# ADC.net
KiCad netlist of a schematic drawn in EAGLE
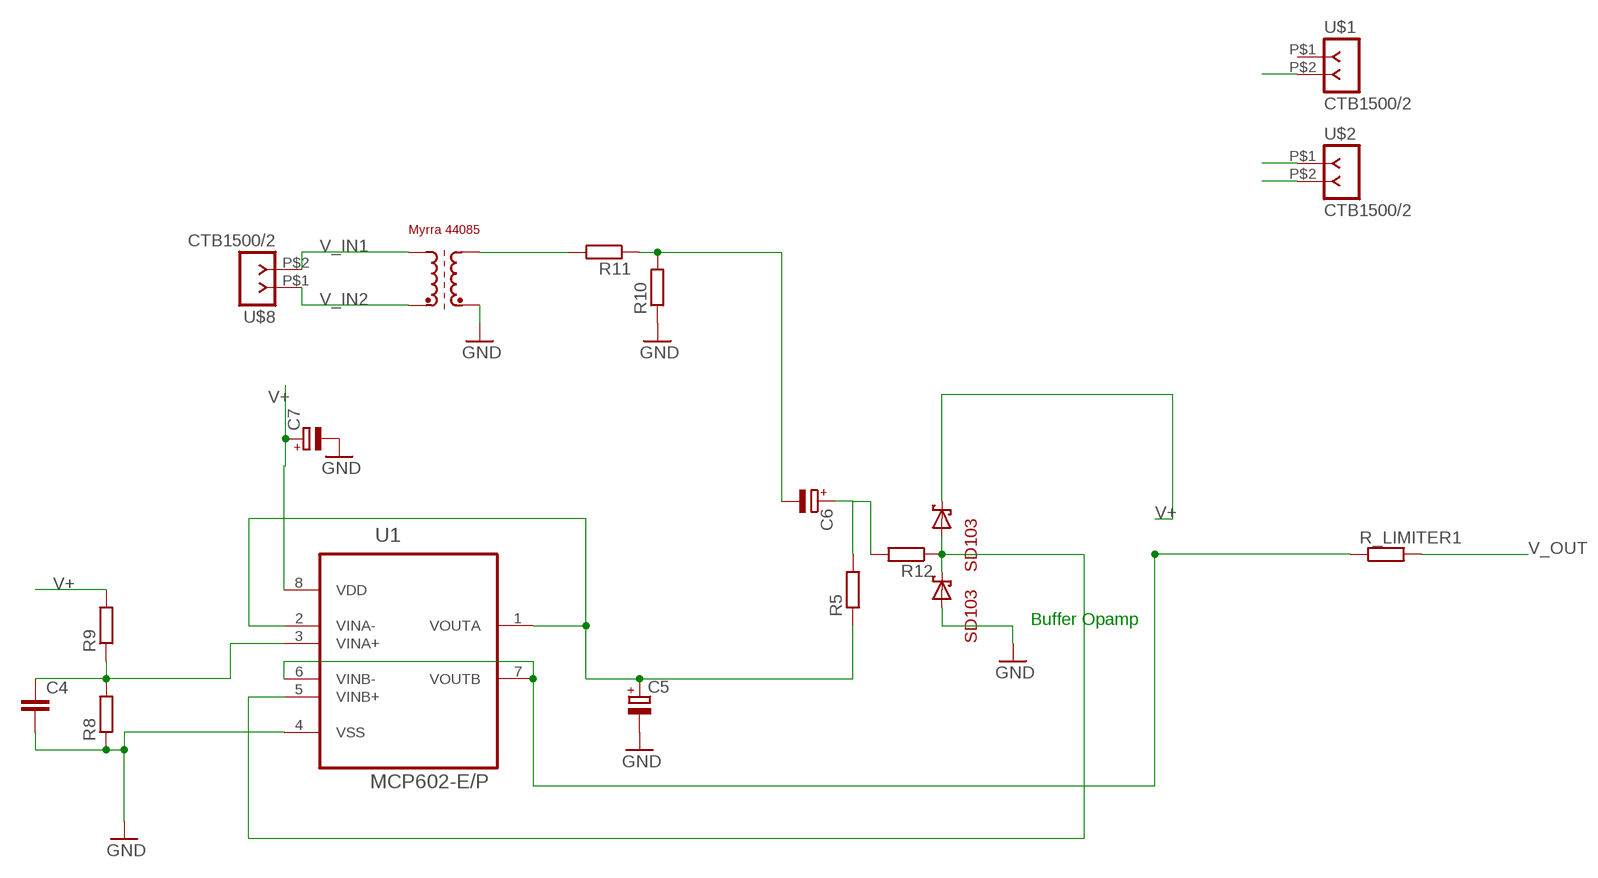
[diagram p0: schematic, sheet 1]

(export (version "E")
  (design (tool "Eeschema 10.0.6"))
  (components
    (comp (ref "C4")
      (value "C5P")
      (footprint "eagle-import:C050-030-075")
      (libsource (lib "eagle-import") (part "C5P"))
    )
    (comp (ref "C5")
      (value "CPOL1")
      (footprint "eagle-import:E2,5-7---100UF")
      (libsource (lib "eagle-import") (part "CPOL1"))
    )
    (comp (ref "C6")
      (value "CPOL1")
      (footprint "eagle-import:E2,5-7---100UF")
      (libsource (lib "eagle-import") (part "CPOL1"))
    )
    (comp (ref "C7")
      (value "CPOL1")
      (footprint "eagle-import:E2,5-7---100UF")
      (libsource (lib "eagle-import") (part "CPOL1"))
    )
    (comp (ref "R5")
      (value "R")
      (footprint "eagle-import:0207_10")
      (libsource (lib "eagle-import") (part "R"))
    )
    (comp (ref "R8")
      (value "R")
      (footprint "eagle-import:0207_10")
      (libsource (lib "eagle-import") (part "R"))
    )
    (comp (ref "R9")
      (value "R")
      (footprint "eagle-import:0207_10")
      (libsource (lib "eagle-import") (part "R"))
    )
    (comp (ref "R10")
      (value "R")
      (footprint "eagle-import:0207_10")
      (libsource (lib "eagle-import") (part "R"))
    )
    (comp (ref "R11")
      (value "R")
      (footprint "eagle-import:0207_10")
      (libsource (lib "eagle-import") (part "R"))
    )
    (comp (ref "R12")
      (value "R")
      (footprint "eagle-import:0207_10")
      (libsource (lib "eagle-import") (part "R"))
    )
    (comp (ref "R_LIMITER1")
      (value "R")
      (footprint "eagle-import:0207_10")
      (libsource (lib "eagle-import") (part "R"))
    )
    (comp (ref "U$1")
      (value "CTB1500/2")
      (footprint "eagle-import:CTB1500-2")
      (libsource (lib "eagle-import") (part "CTB1500/2"))
    )
    (comp (ref "U$2")
      (value "CTB1500/2")
      (footprint "eagle-import:CTB1500-2")
      (libsource (lib "eagle-import") (part "CTB1500/2"))
    )
    (comp (ref "U$5")
      (value "MYRRA_4408")
      (footprint "eagle-import:4408")
      (libsource (lib "eagle-import") (part "MYRRA_4408"))
    )
    (comp (ref "U$6")
      (value "SD103A")
      (footprint "eagle-import:D035-10")
      (libsource (lib "eagle-import") (part "SD103A"))
    )
    (comp (ref "U$7")
      (value "SD103A")
      (footprint "eagle-import:D035-10")
      (libsource (lib "eagle-import") (part "SD103A"))
    )
    (comp (ref "U$8")
      (value "CTB1500/2")
      (footprint "eagle-import:CTB1500-2")
      (libsource (lib "eagle-import") (part "CTB1500/2"))
    )
    (comp (ref "U1")
      (value "MCP602-E/P")
      (footprint "eagle-import:DIP254P762X508-8P")
      (libsource (lib "eagle-import") (part "MCP602-E/P"))
    )
  )
  (nets
    (net (code "1") (name "/N$1") (class "Default")
      (node (ref "R_LIMITER1") (pin "1") (pinfunction "1_1") (pintype "passive"))
      (node (ref "U1") (pin "6") (pinfunction "VINB-_6") (pintype "input"))
      (node (ref "U1") (pin "7") (pinfunction "VOUTB_7") (pintype "output"))
    )
    (net (code "2") (name "/V+") (class "Default")
      (node (ref "C7") (pin "+") (pinfunction "+_+") (pintype "passive"))
      (node (ref "R9") (pin "2") (pinfunction "2_2") (pintype "passive"))
      (node (ref "U$1") (pin "P$2") (pinfunction "2_P$2") (pintype "passive"))
      (node (ref "U$6") (pin "C") (pinfunction "C_C") (pintype "passive"))
      (node (ref "U1") (pin "8") (pinfunction "VDD_8") (pintype "power_in"))
    )
    (net (code "3") (name "/V_IN1") (class "Default")
      (node (ref "U$5") (pin "PIN5") (pinfunction "A1_PIN5") (pintype "passive"))
      (node (ref "U$8") (pin "P$2") (pinfunction "2_P$2") (pintype "passive"))
    )
    (net (code "4") (name "/V_IN2") (class "Default")
      (node (ref "U$5") (pin "PIN1") (pinfunction "E1_PIN1") (pintype "passive"))
      (node (ref "U$8") (pin "P$1") (pinfunction "1_P$1") (pintype "passive"))
    )
    (net (code "5") (name "/V_OUT") (class "Default")
      (node (ref "R_LIMITER1") (pin "2") (pinfunction "2_2") (pintype "passive"))
      (node (ref "U$2") (pin "P$2") (pinfunction "2_P$2") (pintype "passive"))
    )
    (net (code "6") (name "GND") (class "Default")
      (node (ref "C4") (pin "2") (pinfunction "2_2") (pintype "passive"))
      (node (ref "C5") (pin "-") (pinfunction "-_-") (pintype "passive"))
      (node (ref "C7") (pin "-") (pinfunction "-_-") (pintype "passive"))
      (node (ref "R10") (pin "1") (pinfunction "1_1") (pintype "passive"))
      (node (ref "R8") (pin "1") (pinfunction "1_1") (pintype "passive"))
      (node (ref "U$2") (pin "P$1") (pinfunction "1_P$1") (pintype "passive"))
      (node (ref "U$5") (pin "PIN9") (pinfunction "E2_PIN9") (pintype "passive"))
      (node (ref "U$7") (pin "A") (pinfunction "A_A") (pintype "passive"))
      (node (ref "U1") (pin "4") (pinfunction "VSS_4") (pintype "power_in"))
    )
    (net (code "7") (name "Net-(C6-Pad+)") (class "Default")
      (node (ref "C6") (pin "+") (pinfunction "+_+") (pintype "passive"))
      (node (ref "R12") (pin "2") (pinfunction "2_2") (pintype "passive"))
      (node (ref "R5") (pin "2") (pinfunction "2_2") (pintype "passive"))
    )
    (net (code "8") (name "Net-(C6-Pad-)") (class "Default")
      (node (ref "C6") (pin "-") (pinfunction "-_-") (pintype "passive"))
      (node (ref "R10") (pin "2") (pinfunction "2_2") (pintype "passive"))
      (node (ref "R11") (pin "1") (pinfunction "1_1") (pintype "passive"))
    )
    (net (code "9") (name "Net-(U$5-A2)") (class "Default")
      (node (ref "R11") (pin "2") (pinfunction "2_2") (pintype "passive"))
      (node (ref "U$5") (pin "PIN7") (pinfunction "A2_PIN7") (pintype "passive"))
    )
    (net (code "10") (name "Net-(U1-VINA+)") (class "Default")
      (node (ref "C4") (pin "1") (pinfunction "1_1") (pintype "passive"))
      (node (ref "R8") (pin "2") (pinfunction "2_2") (pintype "passive"))
      (node (ref "R9") (pin "1") (pinfunction "1_1") (pintype "passive"))
      (node (ref "U1") (pin "3") (pinfunction "VINA+_3") (pintype "input"))
    )
    (net (code "11") (name "Net-(U1-VINA-)") (class "Default")
      (node (ref "C5") (pin "+") (pinfunction "+_+") (pintype "passive"))
      (node (ref "R5") (pin "1") (pinfunction "1_1") (pintype "passive"))
      (node (ref "U1") (pin "1") (pinfunction "VOUTA_1") (pintype "output"))
      (node (ref "U1") (pin "2") (pinfunction "VINA-_2") (pintype "input"))
    )
    (net (code "12") (name "Net-(U1-VINB+)") (class "Default")
      (node (ref "R12") (pin "1") (pinfunction "1_1") (pintype "passive"))
      (node (ref "U$6") (pin "A") (pinfunction "A_A") (pintype "passive"))
      (node (ref "U$7") (pin "C") (pinfunction "C_C") (pintype "passive"))
      (node (ref "U1") (pin "5") (pinfunction "VINB+_5") (pintype "input"))
    )
    (net (code "13") (name "unconnected-(U$1-1-PadP$1)") (class "Default")
      (node (ref "U$1") (pin "P$1") (pinfunction "1_P$1") (pintype "passive"))
    )
  )
)
